# SCH_Hacker-Card_2024-08-12.net
KiCad netlist of a schematic drawn in EasyEDA
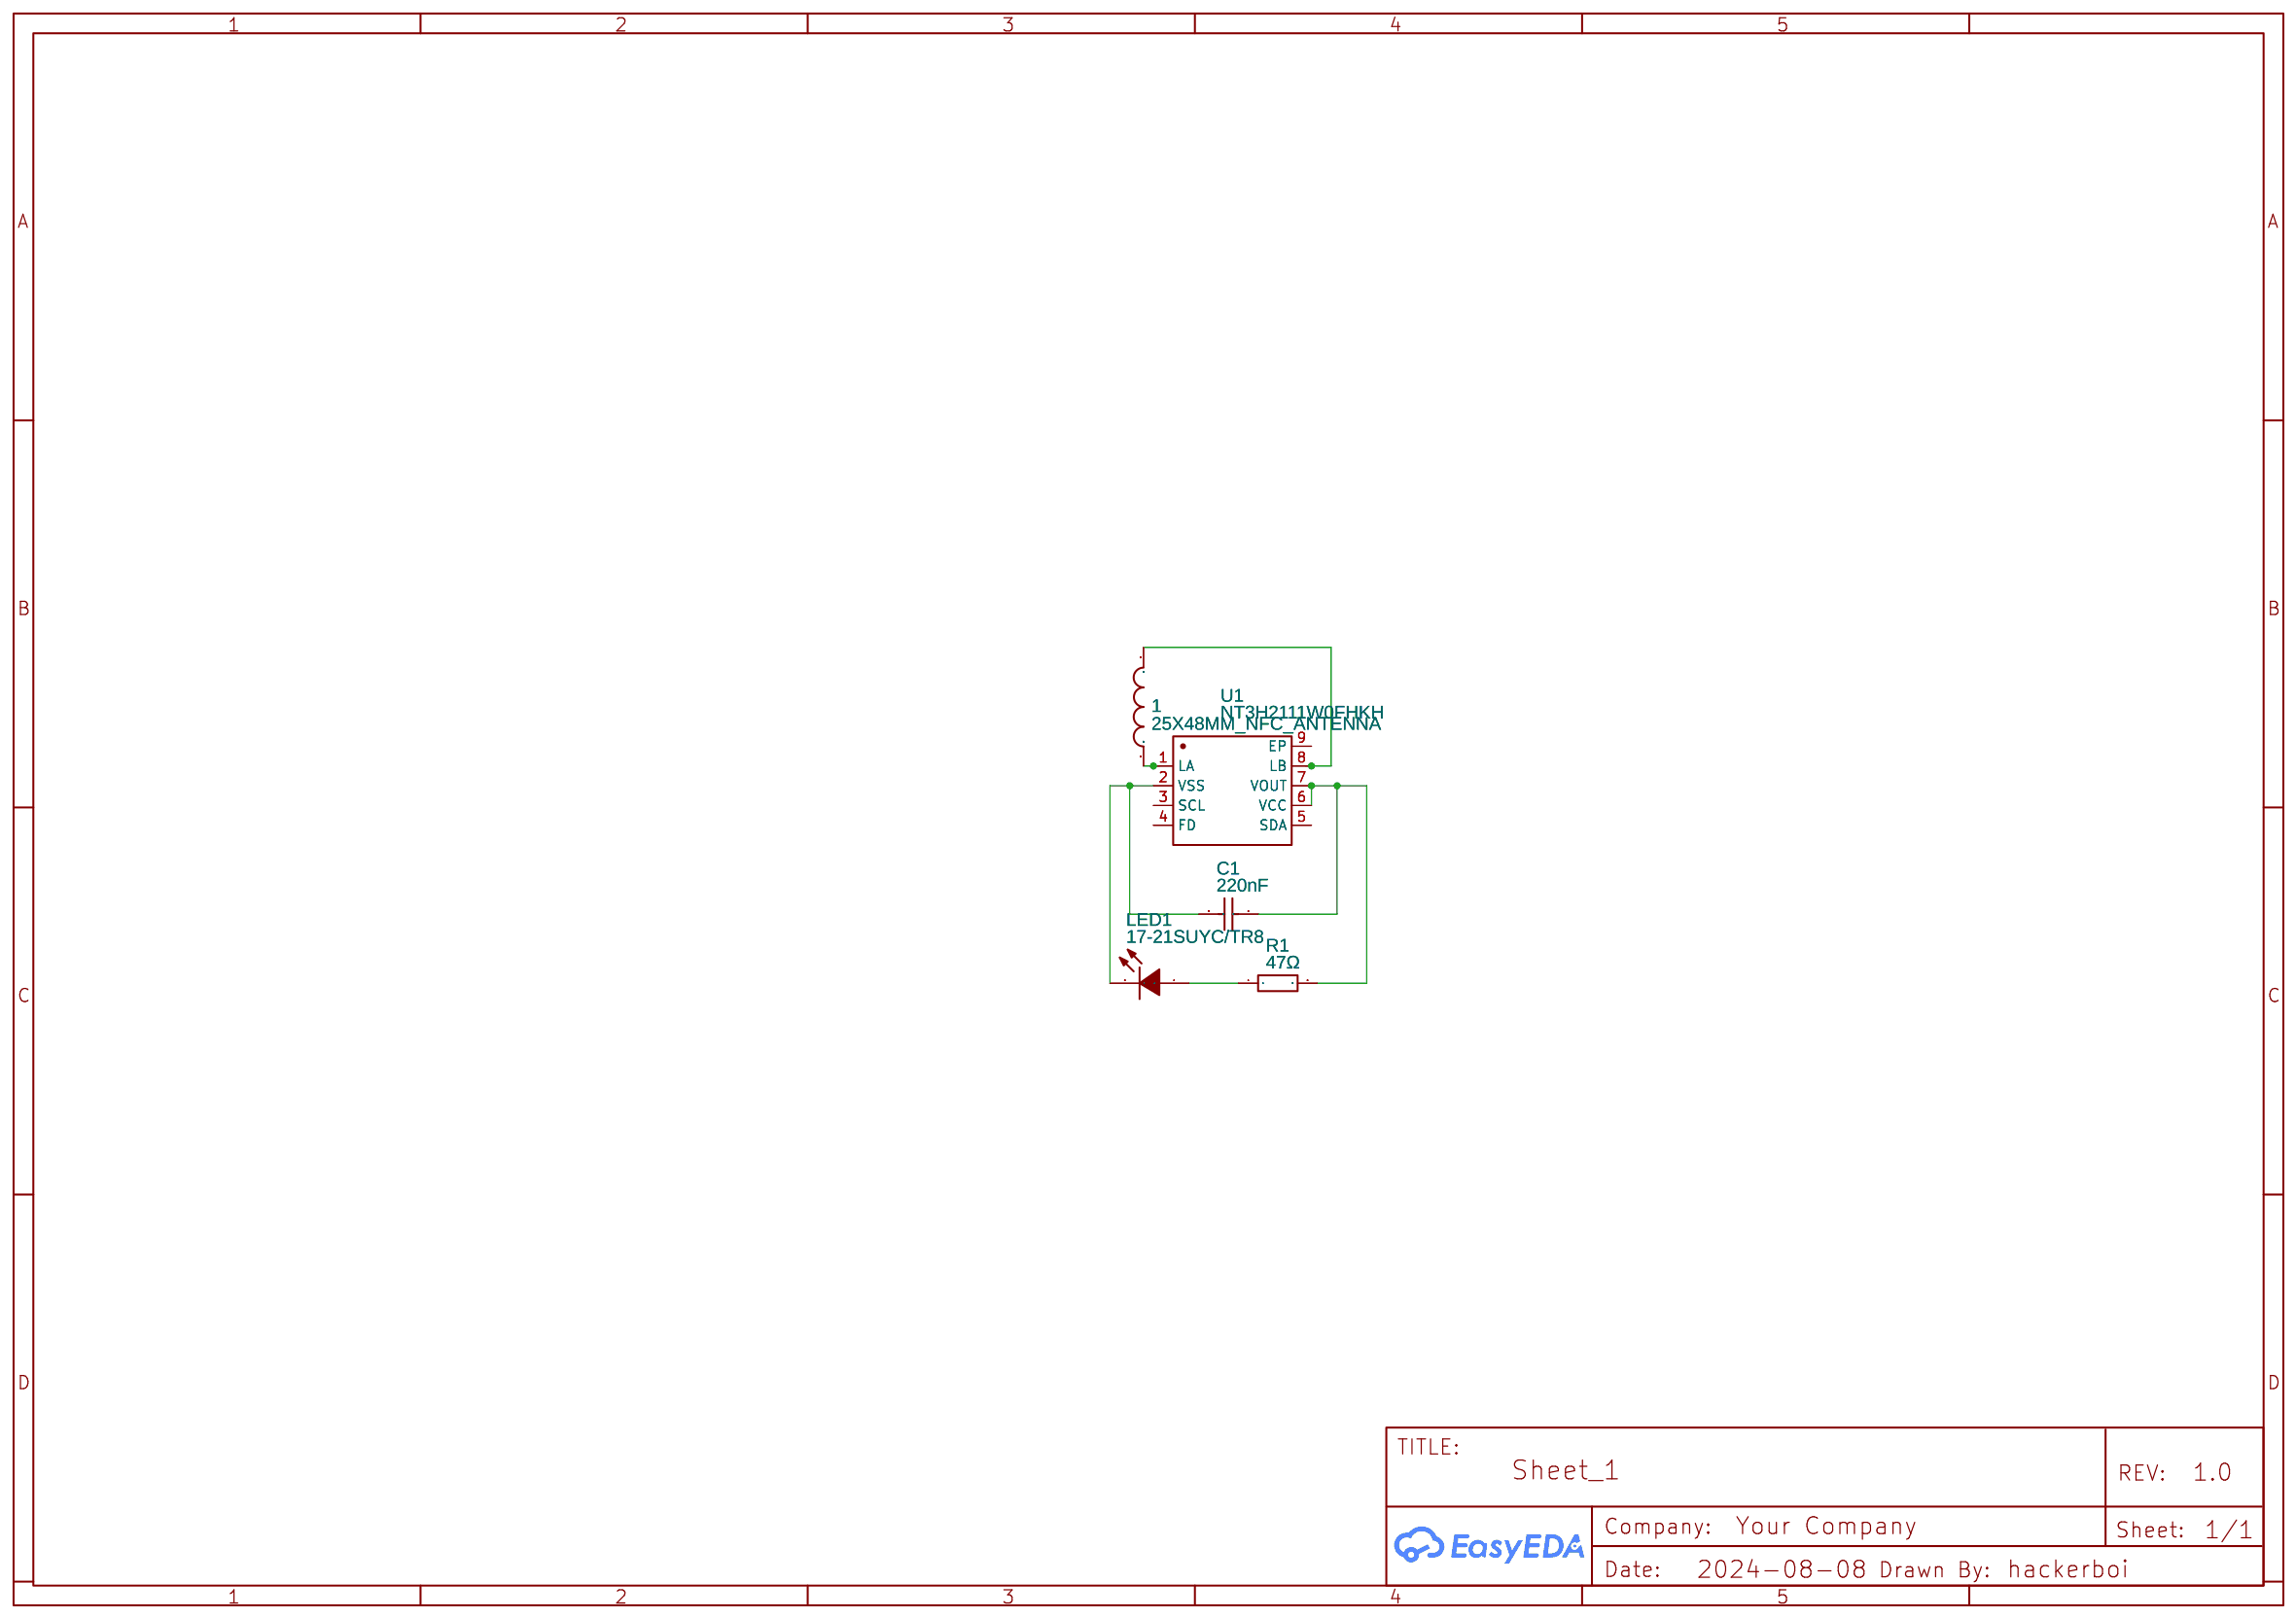
[diagram p0: schematic sheet]

(export (version "E")
  (design (tool "Eeschema 10.0.6"))
  (components
    (comp (ref "1") (value "25X48MM_NFC_ANTENNA") (libsource (lib "") (part "25X48MM_NFC_ANTENNA")))
    (comp (ref "C1")
      (value "220nF")
      (fields
        (field (name "Manufacturer Part") "CL10B224KA8NNNC")
        (field (name "Manufacturer") "SAMSUNG(三星)")
      )
      (libsource (lib "") (part "CL10B224KA8NNNC"))
    )
    (comp (ref "LED1")
      (value "17-21SUYC/TR8")
      (fields (field (name "Manufacturer Part") "KT-0805黄灯") (field (name "Manufacturer") "KENTO"))
      (libsource (lib "") (part "17-21SUYC/TR8"))
    )
    (comp (ref "R1")
      (value "47Ω")
      (fields
        (field (name "Manufacturer Part") "0603WAF470JT5E")
        (field (name "Manufacturer") "UNI-ROYAL(厚声)")
      )
      (libsource (lib "") (part "0603WAF470JT5E"))
    )
    (comp (ref "U1")
      (value "NT3H2111W0FHKH")
      (fields (field (name "Manufacturer") "NXP(恩智浦)"))
      (libsource (lib "") (part "NT3H2111W0FHKH"))
    )
  )
  (nets
    (net (code "1") (name "Net-(LED1-+)") (class "Default")
      (node (ref "LED1") (pin "1") (pinfunction "+_1") (pintype "unspecified"))
      (node (ref "R1") (pin "1") (pinfunction "1_1") (pintype "input"))
    )
    (net (code "2") (name "Net-(LED1--)") (class "Default")
      (node (ref "C1") (pin "1") (pinfunction "1_1") (pintype "input"))
      (node (ref "LED1") (pin "2") (pinfunction "-_2") (pintype "unspecified"))
      (node (ref "U1") (pin "2") (pinfunction "VSS_2") (pintype "unspecified"))
    )
    (net (code "3") (name "Net-(U1-LA)") (class "Default")
      (node (ref "1") (pin "P$1") (pinfunction "P$1_P$1") (pintype "bidirectional"))
      (node (ref "U1") (pin "1") (pinfunction "LA_1") (pintype "unspecified"))
    )
    (net (code "4") (name "Net-(U1-LB)") (class "Default")
      (node (ref "1") (pin "P$2") (pinfunction "P$2_P$2") (pintype "bidirectional"))
      (node (ref "U1") (pin "8") (pinfunction "LB_8") (pintype "unspecified"))
    )
    (net (code "5") (name "Net-(U1-VCC)") (class "Default")
      (node (ref "C1") (pin "2") (pinfunction "2_2") (pintype "input"))
      (node (ref "R1") (pin "2") (pinfunction "2_2") (pintype "input"))
      (node (ref "U1") (pin "6") (pinfunction "VCC_6") (pintype "unspecified"))
      (node (ref "U1") (pin "7") (pinfunction "VOUT_7") (pintype "unspecified"))
    )
    (net (code "6") (name "unconnected-(U1-EP-Pad9)") (class "Default")
      (node (ref "U1") (pin "9") (pinfunction "EP_9") (pintype "unspecified"))
    )
    (net (code "7") (name "unconnected-(U1-FD-Pad4)") (class "Default")
      (node (ref "U1") (pin "4") (pinfunction "FD_4") (pintype "unspecified"))
    )
    (net (code "8") (name "unconnected-(U1-SCL-Pad3)") (class "Default")
      (node (ref "U1") (pin "3") (pinfunction "SCL_3") (pintype "unspecified"))
    )
    (net (code "9") (name "unconnected-(U1-SDA-Pad5)") (class "Default")
      (node (ref "U1") (pin "5") (pinfunction "SDA_5") (pintype "unspecified"))
    )
  )
)
